# Simple-NPN-Regen-Receiver.net
KiCad netlist of a schematic drawn in EAGLE
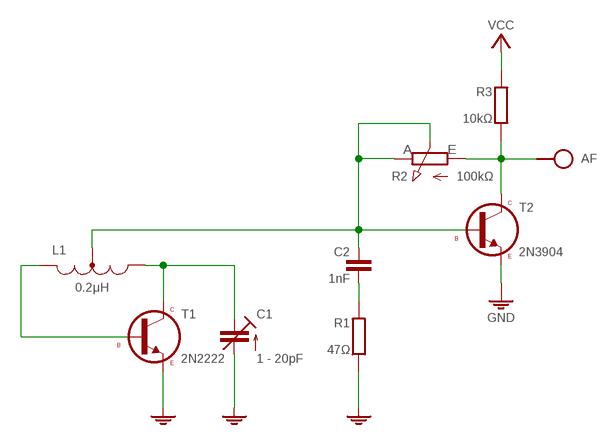
[diagram p0: schematic, sheet 1]

(export (version "E")
  (design (tool "Eeschema 10.0.6"))
  (components
    (comp (ref "AF")
      (value "HPORT")
      (footprint "eagle-import:SPAD")
      (libsource (lib "eagle-import") (part "HPORT"))
    )
    (comp (ref "C1")
      (value "1 - 20pF")
      (footprint "eagle-import:TRIM-2222-808")
      (libsource (lib "eagle-import") (part "C-TR-PH201272222-808-2PINB"))
    )
    (comp (ref "C2")
      (value "1nF")
      (footprint "eagle-import:C025-024X044")
      (libsource (lib "eagle-import") (part "C025-024X044"))
    )
    (comp (ref "L1")
      (value "0.2μH")
      (footprint "eagle-import:L-08_20V-TAPM")
      (libsource (lib "eagle-import") (part "L-H-TAPM-08/20V"))
    )
    (comp (ref "R1")
      (value "47Ω")
      (footprint "eagle-import:0204_10-V")
      (libsource (lib "eagle-import") (part "R0204/10-V"))
    )
    (comp (ref "R2")
      (value "100kΩ")
      (footprint "eagle-import:POT")
      (libsource (lib "eagle-import") (part "POT-H"))
    )
    (comp (ref "R3")
      (value "10kΩ")
      (footprint "eagle-import:0202_10-V")
      (libsource (lib "eagle-import") (part "R0202/10-V"))
    )
    (comp (ref "S3")
      (value "VCC_GNDR")
      (footprint "eagle-import:SPAD+-")
      (libsource (lib "eagle-import") (part "VCC_GNDR"))
    )
    (comp (ref "T1")
      (value "2N2222")
      (footprint "eagle-import:TO92")
      (libsource (lib "eagle-import") (part "2N2222"))
    )
    (comp (ref "T2")
      (value "2N3904")
      (footprint "eagle-import:TO92-EBC-A")
      (libsource (lib "eagle-import") (part "2N3904-A"))
    )
  )
  (nets
    (net (code "1") (name "GND") (class "Default")
      (node (ref "C1") (pin "3") (pinfunction "A_3") (pintype "passive"))
      (node (ref "R1") (pin "2") (pinfunction "1_2") (pintype "passive"))
      (node (ref "S3") (pin "1") (pinfunction "GND_1") (pintype "power_in"))
      (node (ref "T1") (pin "3") (pinfunction "E_3") (pintype "passive"))
      (node (ref "T2") (pin "E") (pinfunction "E_E") (pintype "passive"))
    )
    (net (code "2") (name "Net-(AF-P$1)") (class "Default")
      (node (ref "AF") (pin "1") (pinfunction "P$1_1") (pintype "passive"))
      (node (ref "R2") (pin "A") (pinfunction "A_A") (pintype "passive"))
      (node (ref "R3") (pin "2") (pinfunction "1_2") (pintype "passive"))
      (node (ref "T2") (pin "C") (pinfunction "C_C") (pintype "passive"))
    )
    (net (code "3") (name "Net-(C1-E)") (class "Default")
      (node (ref "C1") (pin "2") (pinfunction "E_2") (pintype "passive"))
      (node (ref "L1") (pin "2") (pinfunction "2_2") (pintype "passive"))
      (node (ref "T1") (pin "1") (pinfunction "C_1") (pintype "passive"))
    )
    (net (code "4") (name "Net-(C2-Pad1)") (class "Default")
      (node (ref "C2") (pin "1") (pinfunction "1_1") (pintype "passive"))
      (node (ref "L1") (pin "T") (pinfunction "T_T") (pintype "passive"))
      (node (ref "R2") (pin "E") (pinfunction "E_E") (pintype "passive"))
      (node (ref "R2") (pin "S") (pinfunction "S_S") (pintype "passive"))
      (node (ref "T2") (pin "B") (pinfunction "B_B") (pintype "passive"))
    )
    (net (code "5") (name "Net-(L1-3)") (class "Default")
      (node (ref "L1") (pin "1") (pinfunction "3_1") (pintype "passive"))
      (node (ref "T1") (pin "2") (pinfunction "B_2") (pintype "passive"))
    )
    (net (code "6") (name "Net-(R1-2)") (class "Default")
      (node (ref "C2") (pin "2") (pinfunction "2_2") (pintype "passive"))
      (node (ref "R1") (pin "1") (pinfunction "2_1") (pintype "passive"))
    )
    (net (code "7") (name "Net-(R3-2)") (class "Default")
      (node (ref "R3") (pin "1") (pinfunction "2_1") (pintype "passive"))
      (node (ref "S3") (pin "2") (pinfunction "VCC_2") (pintype "power_in"))
    )
  )
)
